# Margo_schematic_v6.net
KiCad netlist of a schematic drawn in EAGLE
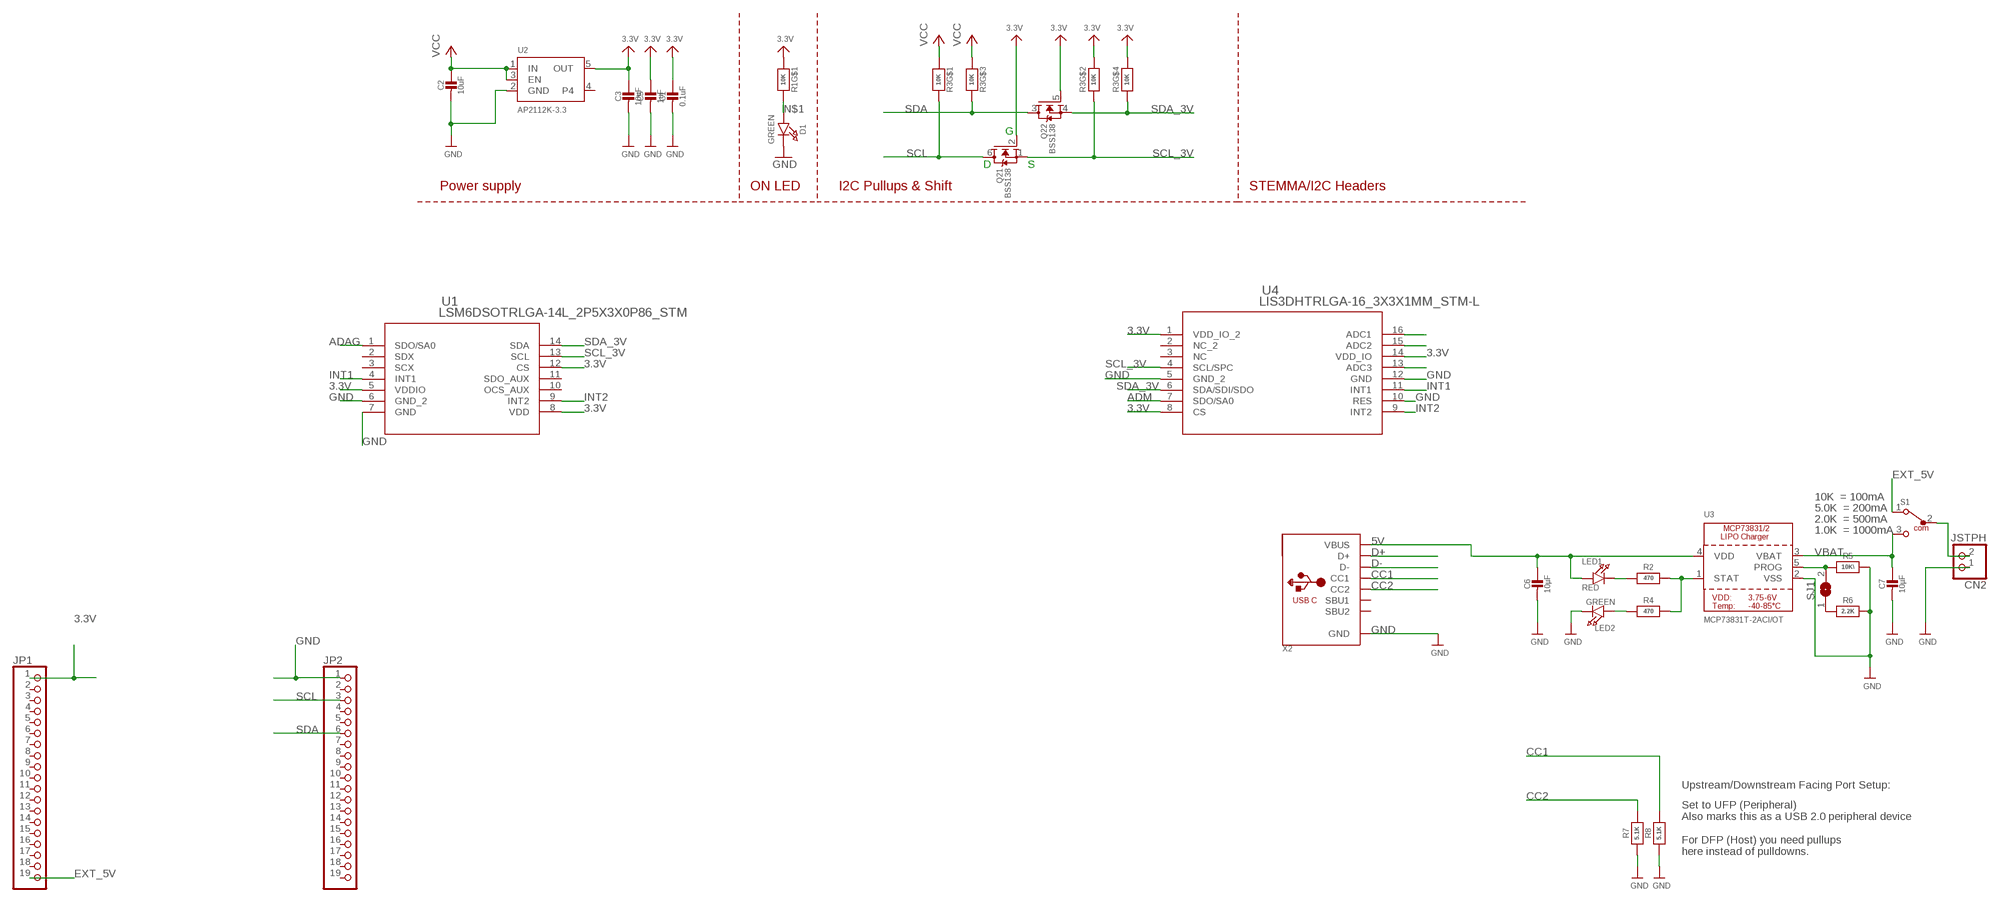
[diagram p0: schematic, sheet 1]

(export (version "E")
  (design (tool "Eeschema 10.0.6"))
  (components
    (comp (ref "C1")
      (value "0.1uF")
      (footprint "eagle-import:0603-NO@1")
      (libsource (lib "eagle-import") (part "CAP_CERAMIC0603_NO"))
    )
    (comp (ref "C2")
      (value "10uF")
      (footprint "eagle-import:0805-NO@1")
      (libsource (lib "eagle-import") (part "CAP_CERAMIC0805-NOOUTLINE"))
    )
    (comp (ref "C3")
      (value "10uF")
      (footprint "eagle-import:0805-NO@1")
      (libsource (lib "eagle-import") (part "CAP_CERAMIC0805-NOOUTLINE"))
    )
    (comp (ref "C5")
      (value "1uF")
      (footprint "eagle-import:0603-NO@1")
      (libsource (lib "eagle-import") (part "CAP_CERAMIC0603_NO"))
    )
    (comp (ref "C6")
      (value "10µF")
      (footprint "eagle-import:0805-NO@1")
      (libsource (lib "eagle-import") (part "CAP_CERAMIC0805-NOOUTLINE"))
    )
    (comp (ref "C7")
      (value "10µF")
      (footprint "eagle-import:0805-NO@1")
      (libsource (lib "eagle-import") (part "CAP_CERAMIC0805-NOOUTLINE"))
    )
    (comp (ref "CN2")
      (value "JSTPH")
      (footprint "eagle-import:JSTPH2")
      (libsource (lib "eagle-import") (part "JST_2PIN"))
    )
    (comp (ref "D1")
      (value "GREEN")
      (footprint "eagle-import:CHIPLED_0603_NOOUTLINE")
      (libsource (lib "eagle-import") (part "LED0603_NOOUTLINE"))
    )
    (comp (ref "JP1")
      (value "PINHD-1X19")
      (footprint "eagle-import:1X19")
      (libsource (lib "eagle-import") (part "PINHD-1X19"))
    )
    (comp (ref "JP2")
      (value "PINHD-1X19")
      (footprint "eagle-import:1X19")
      (libsource (lib "eagle-import") (part "PINHD-1X19"))
    )
    (comp (ref "LED1")
      (value "RED")
      (footprint "eagle-import:CHIPLED_0805_NOOUTLINE")
      (libsource (lib "eagle-import") (part "LED0805_NOOUTLINE"))
    )
    (comp (ref "LED2")
      (value "GREEN")
      (footprint "eagle-import:CHIPLED_0805_NOOUTLINE")
      (libsource (lib "eagle-import") (part "LED0805_NOOUTLINE"))
    )
    (comp (ref "Q2")
      (value "BSS138")
      (footprint "eagle-import:SOT363")
      (libsource (lib "eagle-import") (part "MOSFET-N_DUAL"))
    )
    (comp (ref "R1")
      (value "10K")
      (footprint "eagle-import:RESPACK_4X0603")
      (libsource (lib "eagle-import") (part "RESISTOR_4PACK"))
    )
    (comp (ref "R2")
      (value "470")
      (footprint "eagle-import:0603-NO")
      (libsource (lib "eagle-import") (part "RESISTOR_0603_NOOUT"))
    )
    (comp (ref "R3")
      (value "10K")
      (footprint "eagle-import:RESPACK_4X0603")
      (libsource (lib "eagle-import") (part "RESISTOR_4PACK"))
    )
    (comp (ref "R4")
      (value "470")
      (footprint "eagle-import:0603-NO")
      (libsource (lib "eagle-import") (part "RESISTOR_0603_NOOUT"))
    )
    (comp (ref "R5")
      (value "10K\\")
      (footprint "eagle-import:0603-NO")
      (libsource (lib "eagle-import") (part "RESISTOR_0603_NOOUT"))
    )
    (comp (ref "R6")
      (value "2.2K")
      (footprint "eagle-import:0603-NO")
      (libsource (lib "eagle-import") (part "RESISTOR_0603_NOOUT"))
    )
    (comp (ref "R7")
      (value "5.1K")
      (footprint "eagle-import:0603-NO")
      (libsource (lib "eagle-import") (part "RESISTOR_0603_NOOUT"))
    )
    (comp (ref "R8")
      (value "5.1K")
      (footprint "eagle-import:0603-NO")
      (libsource (lib "eagle-import") (part "RESISTOR_0603_NOOUT"))
    )
    (comp (ref "S1")
      (value "450404015514")
      (footprint "eagle-import:450404015514")
      (libsource (lib "eagle-import") (part "450404015514"))
    )
    (comp (ref "SJ1")
      (value "SOLDERJUMPER")
      (footprint "eagle-import:SOLDERJUMPER_ARROW_NOPASTE")
      (libsource (lib "eagle-import") (part "SOLDERJUMPER"))
    )
    (comp (ref "U1")
      (value "LSM6DSOTRLGA-14L_2P5X3X0P86_STM")
      (footprint "eagle-import:LGA-14L_2P5X3X0P86_STM")
      (fields
        (field (name "MANUFACTURER_PART_NUMBER") "LSM6DSOTR")
        (field (name "COPYRIGHT") "Copyright (C) 2023 Ultra Librarian. All rights reserved.")
      )
      (libsource (lib "eagle-import") (part "LSM6DSOTRLGA-14L_2P5X3X0P86_STM"))
    )
    (comp (ref "U2")
      (value "AP2112K-3.3")
      (footprint "eagle-import:SOT23-5")
      (libsource (lib "eagle-import") (part "VREG_SOT23-5"))
    )
    (comp (ref "U3")
      (value "MCP73831T-2ACI/OT")
      (footprint "eagle-import:SOT23-5")
      (libsource (lib "eagle-import") (part "MCP73831/2"))
    )
    (comp (ref "U4")
      (value "LIS3DHTRLGA-16_3X3X1MM_STM-L")
      (footprint "eagle-import:LGA-16_3X3X1MM_STM-L")
      (fields
        (field (name "MANUFACTURER_PART_NUMBER") "LIS3DHTR")
        (field (name "COPYRIGHT") "Copyright (C) 2023 Ultra Librarian. All rights reserved.")
      )
      (libsource (lib "eagle-import") (part "LIS3DHTRLGA-16_3X3X1MM_STM-L"))
    )
    (comp (ref "X2")
      (value "USB_C")
      (footprint "eagle-import:USB_C_CUSB31-CFM2AX-01-X")
      (libsource (lib "eagle-import") (part "USB_C"))
    )
  )
  (nets
    (net (code "1") (name "/5V") (class "Default")
      (node (ref "C6") (pin "1") (pinfunction "1_1") (pintype "passive"))
      (node (ref "LED1") (pin "A") (pinfunction "A_A") (pintype "passive"))
      (node (ref "U3") (pin "4") (pinfunction "VDD_4") (pintype "power_in"))
      (node (ref "X2") (pin "A4B9") (pinfunction "VBUS_A4B9") (pintype "power_in"))
      (node (ref "X2") (pin "B4A9") (pinfunction "VBUS_B4A9") (pintype "power_in"))
    )
    (net (code "2") (name "/ADAG") (class "Default")
      (node (ref "U1") (pin "1") (pinfunction "SDO/SA0_1") (pintype "bidirectional"))
    )
    (net (code "3") (name "/ADM") (class "Default")
      (node (ref "U4") (pin "7") (pinfunction "SDO/SA0_7") (pintype "passive"))
    )
    (net (code "4") (name "/CC1") (class "Default")
      (node (ref "R8") (pin "2") (pinfunction "2_2") (pintype "passive"))
      (node (ref "X2") (pin "A5") (pinfunction "CC1_A5") (pintype "bidirectional"))
    )
    (net (code "5") (name "/CC2") (class "Default")
      (node (ref "R7") (pin "2") (pinfunction "2_2") (pintype "passive"))
      (node (ref "X2") (pin "B5") (pinfunction "CC2_B5") (pintype "bidirectional"))
    )
    (net (code "6") (name "/D+") (class "Default")
      (node (ref "X2") (pin "A6") (pinfunction "D+_A6") (pintype "bidirectional"))
      (node (ref "X2") (pin "B6") (pinfunction "D+_B6") (pintype "bidirectional"))
    )
    (net (code "7") (name "/D-") (class "Default")
      (node (ref "X2") (pin "A7") (pinfunction "D-_A7") (pintype "bidirectional"))
      (node (ref "X2") (pin "B7") (pinfunction "D-_B7") (pintype "bidirectional"))
    )
    (net (code "8") (name "/EXT_5V") (class "Default")
      (node (ref "JP1") (pin "19") (pinfunction "19_19") (pintype "passive"))
      (node (ref "S1") (pin "1") (pinfunction "1_1") (pintype "passive"))
    )
    (net (code "9") (name "/INT1") (class "Default")
      (node (ref "U1") (pin "4") (pinfunction "INT1_4") (pintype "output"))
      (node (ref "U4") (pin "11") (pinfunction "INT1_11") (pintype "passive"))
    )
    (net (code "10") (name "/INT2") (class "Default")
      (node (ref "U1") (pin "9") (pinfunction "INT2_9") (pintype "output"))
      (node (ref "U4") (pin "9") (pinfunction "INT2_9") (pintype "passive"))
    )
    (net (code "11") (name "/N$1") (class "Default")
      (node (ref "D1") (pin "A") (pinfunction "A_A") (pintype "passive"))
      (node (ref "R1") (pin "8") (pinfunction "2_8") (pintype "passive"))
    )
    (net (code "12") (name "/SCL") (class "Default")
      (node (ref "JP2") (pin "3") (pinfunction "3_3") (pintype "passive"))
      (node (ref "Q2") (pin "6") (pinfunction "D_6") (pintype "bidirectional"))
      (node (ref "R3") (pin "8") (pinfunction "2_8") (pintype "passive"))
    )
    (net (code "13") (name "/SCL_3V") (class "Default")
      (node (ref "Q2") (pin "1") (pinfunction "S_1") (pintype "bidirectional"))
      (node (ref "R3") (pin "7") (pinfunction "2_7") (pintype "passive"))
      (node (ref "U1") (pin "13") (pinfunction "SCL_13") (pintype "input"))
      (node (ref "U4") (pin "4") (pinfunction "SCL/SPC_4") (pintype "passive"))
    )
    (net (code "14") (name "/SDA") (class "Default")
      (node (ref "JP2") (pin "6") (pinfunction "6_6") (pintype "passive"))
      (node (ref "Q2") (pin "3") (pinfunction "D_3") (pintype "bidirectional"))
      (node (ref "R3") (pin "6") (pinfunction "2_6") (pintype "passive"))
    )
    (net (code "15") (name "/SDA_3V") (class "Default")
      (node (ref "Q2") (pin "4") (pinfunction "S_4") (pintype "bidirectional"))
      (node (ref "R3") (pin "5") (pinfunction "2_5") (pintype "passive"))
      (node (ref "U1") (pin "14") (pinfunction "SDA_14") (pintype "bidirectional"))
      (node (ref "U4") (pin "6") (pinfunction "SDA/SDI/SDO_6") (pintype "passive"))
    )
    (net (code "16") (name "/VBAT") (class "Default")
      (node (ref "C7") (pin "1") (pinfunction "1_1") (pintype "passive"))
      (node (ref "S1") (pin "3") (pinfunction "3_3") (pintype "passive"))
      (node (ref "U3") (pin "3") (pinfunction "VBAT_3") (pintype "power_in"))
    )
    (net (code "17") (name "3.3V") (class "Default")
      (node (ref "C1") (pin "1") (pinfunction "1_1") (pintype "passive"))
      (node (ref "C3") (pin "1") (pinfunction "1_1") (pintype "passive"))
      (node (ref "C5") (pin "1") (pinfunction "1_1") (pintype "passive"))
      (node (ref "JP1") (pin "1") (pinfunction "1_1") (pintype "passive"))
      (node (ref "Q2") (pin "2") (pinfunction "G_2") (pintype "bidirectional"))
      (node (ref "Q2") (pin "5") (pinfunction "G_5") (pintype "bidirectional"))
      (node (ref "R1") (pin "1") (pinfunction "1_1") (pintype "passive"))
      (node (ref "R3") (pin "2") (pinfunction "1_2") (pintype "passive"))
      (node (ref "R3") (pin "4") (pinfunction "1_4") (pintype "passive"))
      (node (ref "U1") (pin "12") (pinfunction "CS_12") (pintype "input"))
      (node (ref "U1") (pin "5") (pinfunction "VDDIO_5") (pintype "power_in"))
      (node (ref "U1") (pin "8") (pinfunction "VDD_8") (pintype "power_in"))
      (node (ref "U2") (pin "5") (pinfunction "OUT_5") (pintype "power_in"))
      (node (ref "U4") (pin "1") (pinfunction "VDD_IO_2_1") (pintype "power_in"))
      (node (ref "U4") (pin "14") (pinfunction "VDD_IO_14") (pintype "power_in"))
      (node (ref "U4") (pin "8") (pinfunction "CS_8") (pintype "passive"))
    )
    (net (code "18") (name "GND") (class "Default")
      (node (ref "C1") (pin "2") (pinfunction "2_2") (pintype "passive"))
      (node (ref "C2") (pin "2") (pinfunction "2_2") (pintype "passive"))
      (node (ref "C3") (pin "2") (pinfunction "2_2") (pintype "passive"))
      (node (ref "C5") (pin "2") (pinfunction "2_2") (pintype "passive"))
      (node (ref "C6") (pin "2") (pinfunction "2_2") (pintype "passive"))
      (node (ref "C7") (pin "2") (pinfunction "2_2") (pintype "passive"))
      (node (ref "CN2") (pin "1") (pinfunction "1_1") (pintype "passive"))
      (node (ref "D1") (pin "C") (pinfunction "C_C") (pintype "passive"))
      (node (ref "JP2") (pin "1") (pinfunction "1_1") (pintype "passive"))
      (node (ref "LED2") (pin "C") (pinfunction "C_C") (pintype "passive"))
      (node (ref "R5") (pin "2") (pinfunction "2_2") (pintype "passive"))
      (node (ref "R6") (pin "2") (pinfunction "2_2") (pintype "passive"))
      (node (ref "R7") (pin "1") (pinfunction "1_1") (pintype "passive"))
      (node (ref "R8") (pin "1") (pinfunction "1_1") (pintype "passive"))
      (node (ref "U1") (pin "6") (pinfunction "GND_2_6") (pintype "passive"))
      (node (ref "U1") (pin "7") (pinfunction "GND_7") (pintype "passive"))
      (node (ref "U2") (pin "2") (pinfunction "GND_2") (pintype "power_in"))
      (node (ref "U3") (pin "2") (pinfunction "VSS_2") (pintype "power_in"))
      (node (ref "U4") (pin "10") (pinfunction "RES_10") (pintype "passive"))
      (node (ref "U4") (pin "12") (pinfunction "GND_12") (pintype "power_in"))
      (node (ref "U4") (pin "5") (pinfunction "GND_2_5") (pintype "power_in"))
      (node (ref "X2") (pin "A1B12") (pinfunction "GND_A1B12") (pintype "power_in"))
      (node (ref "X2") (pin "B1A12") (pinfunction "GND_B1A12") (pintype "power_in"))
    )
    (net (code "19") (name "Net-(CN2-Pad2)") (class "Default")
      (node (ref "CN2") (pin "2") (pinfunction "2_2") (pintype "passive"))
      (node (ref "S1") (pin "2") (pinfunction "2_2") (pintype "passive"))
    )
    (net (code "20") (name "Net-(LED1-PadC)") (class "Default")
      (node (ref "LED1") (pin "C") (pinfunction "C_C") (pintype "passive"))
      (node (ref "R2") (pin "1") (pinfunction "1_1") (pintype "passive"))
    )
    (net (code "21") (name "Net-(LED2-PadA)") (class "Default")
      (node (ref "LED2") (pin "A") (pinfunction "A_A") (pintype "passive"))
      (node (ref "R4") (pin "1") (pinfunction "1_1") (pintype "passive"))
    )
    (net (code "22") (name "Net-(R6-Pad1)") (class "Default")
      (node (ref "R6") (pin "1") (pinfunction "1_1") (pintype "passive"))
      (node (ref "SJ1") (pin "1") (pinfunction "1_1") (pintype "passive"))
    )
    (net (code "23") (name "Net-(U3-PROG)") (class "Default")
      (node (ref "R5") (pin "1") (pinfunction "1_1") (pintype "passive"))
      (node (ref "SJ1") (pin "2") (pinfunction "2_2") (pintype "passive"))
      (node (ref "U3") (pin "5") (pinfunction "PROG_5") (pintype "input"))
    )
    (net (code "24") (name "Net-(U3-STAT)") (class "Default")
      (node (ref "R2") (pin "2") (pinfunction "2_2") (pintype "passive"))
      (node (ref "R4") (pin "2") (pinfunction "2_2") (pintype "passive"))
      (node (ref "U3") (pin "1") (pinfunction "STAT_1") (pintype "output"))
    )
    (net (code "25") (name "VCC") (class "Default")
      (node (ref "C2") (pin "1") (pinfunction "1_1") (pintype "passive"))
      (node (ref "R3") (pin "1") (pinfunction "1_1") (pintype "passive"))
      (node (ref "R3") (pin "3") (pinfunction "1_3") (pintype "passive"))
      (node (ref "U2") (pin "1") (pinfunction "IN_1") (pintype "power_in"))
      (node (ref "U2") (pin "3") (pinfunction "EN_3") (pintype "input"))
    )
    (net (code "26") (name "unconnected-(JP1-Pad2)") (class "Default")
      (node (ref "JP1") (pin "2") (pinfunction "2_2") (pintype "passive"))
    )
    (net (code "27") (name "unconnected-(JP1-Pad3)") (class "Default")
      (node (ref "JP1") (pin "3") (pinfunction "3_3") (pintype "passive"))
    )
    (net (code "28") (name "unconnected-(JP1-Pad4)") (class "Default")
      (node (ref "JP1") (pin "4") (pinfunction "4_4") (pintype "passive"))
    )
    (net (code "29") (name "unconnected-(JP1-Pad5)") (class "Default")
      (node (ref "JP1") (pin "5") (pinfunction "5_5") (pintype "passive"))
    )
    (net (code "30") (name "unconnected-(JP1-Pad6)") (class "Default")
      (node (ref "JP1") (pin "6") (pinfunction "6_6") (pintype "passive"))
    )
    (net (code "31") (name "unconnected-(JP1-Pad7)") (class "Default")
      (node (ref "JP1") (pin "7") (pinfunction "7_7") (pintype "passive"))
    )
    (net (code "32") (name "unconnected-(JP1-Pad8)") (class "Default")
      (node (ref "JP1") (pin "8") (pinfunction "8_8") (pintype "passive"))
    )
    (net (code "33") (name "unconnected-(JP1-Pad9)") (class "Default")
      (node (ref "JP1") (pin "9") (pinfunction "9_9") (pintype "passive"))
    )
    (net (code "34") (name "unconnected-(JP1-Pad10)") (class "Default")
      (node (ref "JP1") (pin "10") (pinfunction "10_10") (pintype "passive"))
    )
    (net (code "35") (name "unconnected-(JP1-Pad11)") (class "Default")
      (node (ref "JP1") (pin "11") (pinfunction "11_11") (pintype "passive"))
    )
    (net (code "36") (name "unconnected-(JP1-Pad12)") (class "Default")
      (node (ref "JP1") (pin "12") (pinfunction "12_12") (pintype "passive"))
    )
    (net (code "37") (name "unconnected-(JP1-Pad13)") (class "Default")
      (node (ref "JP1") (pin "13") (pinfunction "13_13") (pintype "passive"))
    )
    (net (code "38") (name "unconnected-(JP1-Pad14)") (class "Default")
      (node (ref "JP1") (pin "14") (pinfunction "14_14") (pintype "passive"))
    )
    (net (code "39") (name "unconnected-(JP1-Pad15)") (class "Default")
      (node (ref "JP1") (pin "15") (pinfunction "15_15") (pintype "passive"))
    )
    (net (code "40") (name "unconnected-(JP1-Pad16)") (class "Default")
      (node (ref "JP1") (pin "16") (pinfunction "16_16") (pintype "passive"))
    )
    (net (code "41") (name "unconnected-(JP1-Pad17)") (class "Default")
      (node (ref "JP1") (pin "17") (pinfunction "17_17") (pintype "passive"))
    )
    (net (code "42") (name "unconnected-(JP1-Pad18)") (class "Default")
      (node (ref "JP1") (pin "18") (pinfunction "18_18") (pintype "passive"))
    )
    (net (code "43") (name "unconnected-(JP2-Pad2)") (class "Default")
      (node (ref "JP2") (pin "2") (pinfunction "2_2") (pintype "passive"))
    )
    (net (code "44") (name "unconnected-(JP2-Pad4)") (class "Default")
      (node (ref "JP2") (pin "4") (pinfunction "4_4") (pintype "passive"))
    )
    (net (code "45") (name "unconnected-(JP2-Pad5)") (class "Default")
      (node (ref "JP2") (pin "5") (pinfunction "5_5") (pintype "passive"))
    )
    (net (code "46") (name "unconnected-(JP2-Pad7)") (class "Default")
      (node (ref "JP2") (pin "7") (pinfunction "7_7") (pintype "passive"))
    )
    (net (code "47") (name "unconnected-(JP2-Pad8)") (class "Default")
      (node (ref "JP2") (pin "8") (pinfunction "8_8") (pintype "passive"))
    )
    (net (code "48") (name "unconnected-(JP2-Pad9)") (class "Default")
      (node (ref "JP2") (pin "9") (pinfunction "9_9") (pintype "passive"))
    )
    (net (code "49") (name "unconnected-(JP2-Pad10)") (class "Default")
      (node (ref "JP2") (pin "10") (pinfunction "10_10") (pintype "passive"))
    )
    (net (code "50") (name "unconnected-(JP2-Pad11)") (class "Default")
      (node (ref "JP2") (pin "11") (pinfunction "11_11") (pintype "passive"))
    )
    (net (code "51") (name "unconnected-(JP2-Pad12)") (class "Default")
      (node (ref "JP2") (pin "12") (pinfunction "12_12") (pintype "passive"))
    )
    (net (code "52") (name "unconnected-(JP2-Pad13)") (class "Default")
      (node (ref "JP2") (pin "13") (pinfunction "13_13") (pintype "passive"))
    )
    (net (code "53") (name "unconnected-(JP2-Pad14)") (class "Default")
      (node (ref "JP2") (pin "14") (pinfunction "14_14") (pintype "passive"))
    )
    (net (code "54") (name "unconnected-(JP2-Pad15)") (class "Default")
      (node (ref "JP2") (pin "15") (pinfunction "15_15") (pintype "passive"))
    )
    (net (code "55") (name "unconnected-(JP2-Pad16)") (class "Default")
      (node (ref "JP2") (pin "16") (pinfunction "16_16") (pintype "passive"))
    )
    (net (code "56") (name "unconnected-(JP2-Pad17)") (class "Default")
      (node (ref "JP2") (pin "17") (pinfunction "17_17") (pintype "passive"))
    )
    (net (code "57") (name "unconnected-(JP2-Pad18)") (class "Default")
      (node (ref "JP2") (pin "18") (pinfunction "18_18") (pintype "passive"))
    )
    (net (code "58") (name "unconnected-(JP2-Pad19)") (class "Default")
      (node (ref "JP2") (pin "19") (pinfunction "19_19") (pintype "passive"))
    )
    (net (code "59") (name "unconnected-(U1-OCS_AUX-Pad10)") (class "Default")
      (node (ref "U1") (pin "10") (pinfunction "OCS_AUX_10") (pintype "bidirectional"))
    )
    (net (code "60") (name "unconnected-(U1-SCX-Pad3)") (class "Default")
      (node (ref "U1") (pin "3") (pinfunction "SCX_3") (pintype "bidirectional"))
    )
    (net (code "61") (name "unconnected-(U1-SDO_AUX-Pad11)") (class "Default")
      (node (ref "U1") (pin "11") (pinfunction "SDO_AUX_11") (pintype "bidirectional"))
    )
    (net (code "62") (name "unconnected-(U1-SDX-Pad2)") (class "Default")
      (node (ref "U1") (pin "2") (pinfunction "SDX_2") (pintype "bidirectional"))
    )
    (net (code "63") (name "unconnected-(U2-P4-Pad4)") (class "Default")
      (node (ref "U2") (pin "4") (pinfunction "P4_4") (pintype "bidirectional"))
    )
    (net (code "64") (name "unconnected-(U4-ADC1-Pad16)") (class "Default")
      (node (ref "U4") (pin "16") (pinfunction "ADC1_16") (pintype "input"))
    )
    (net (code "65") (name "unconnected-(U4-ADC2-Pad15)") (class "Default")
      (node (ref "U4") (pin "15") (pinfunction "ADC2_15") (pintype "input"))
    )
    (net (code "66") (name "unconnected-(U4-ADC3-Pad13)") (class "Default")
      (node (ref "U4") (pin "13") (pinfunction "ADC3_13") (pintype "input"))
    )
    (net (code "67") (name "unconnected-(U4-NC-Pad3)") (class "Default")
      (node (ref "U4") (pin "3") (pinfunction "NC_3") (pintype "no_connect"))
    )
    (net (code "68") (name "unconnected-(U4-NC_2-Pad2)") (class "Default")
      (node (ref "U4") (pin "2") (pinfunction "NC_2_2") (pintype "no_connect"))
    )
    (net (code "69") (name "unconnected-(X2-SBU1-PadA8)") (class "Default")
      (node (ref "X2") (pin "A8") (pinfunction "SBU1_A8") (pintype "bidirectional"))
    )
    (net (code "70") (name "unconnected-(X2-SBU2-PadB8)") (class "Default")
      (node (ref "X2") (pin "B8") (pinfunction "SBU2_B8") (pintype "bidirectional"))
    )
  )
)
